# Arduino_NRF24_RevD.net
KiCad netlist of a schematic drawn in EAGLE
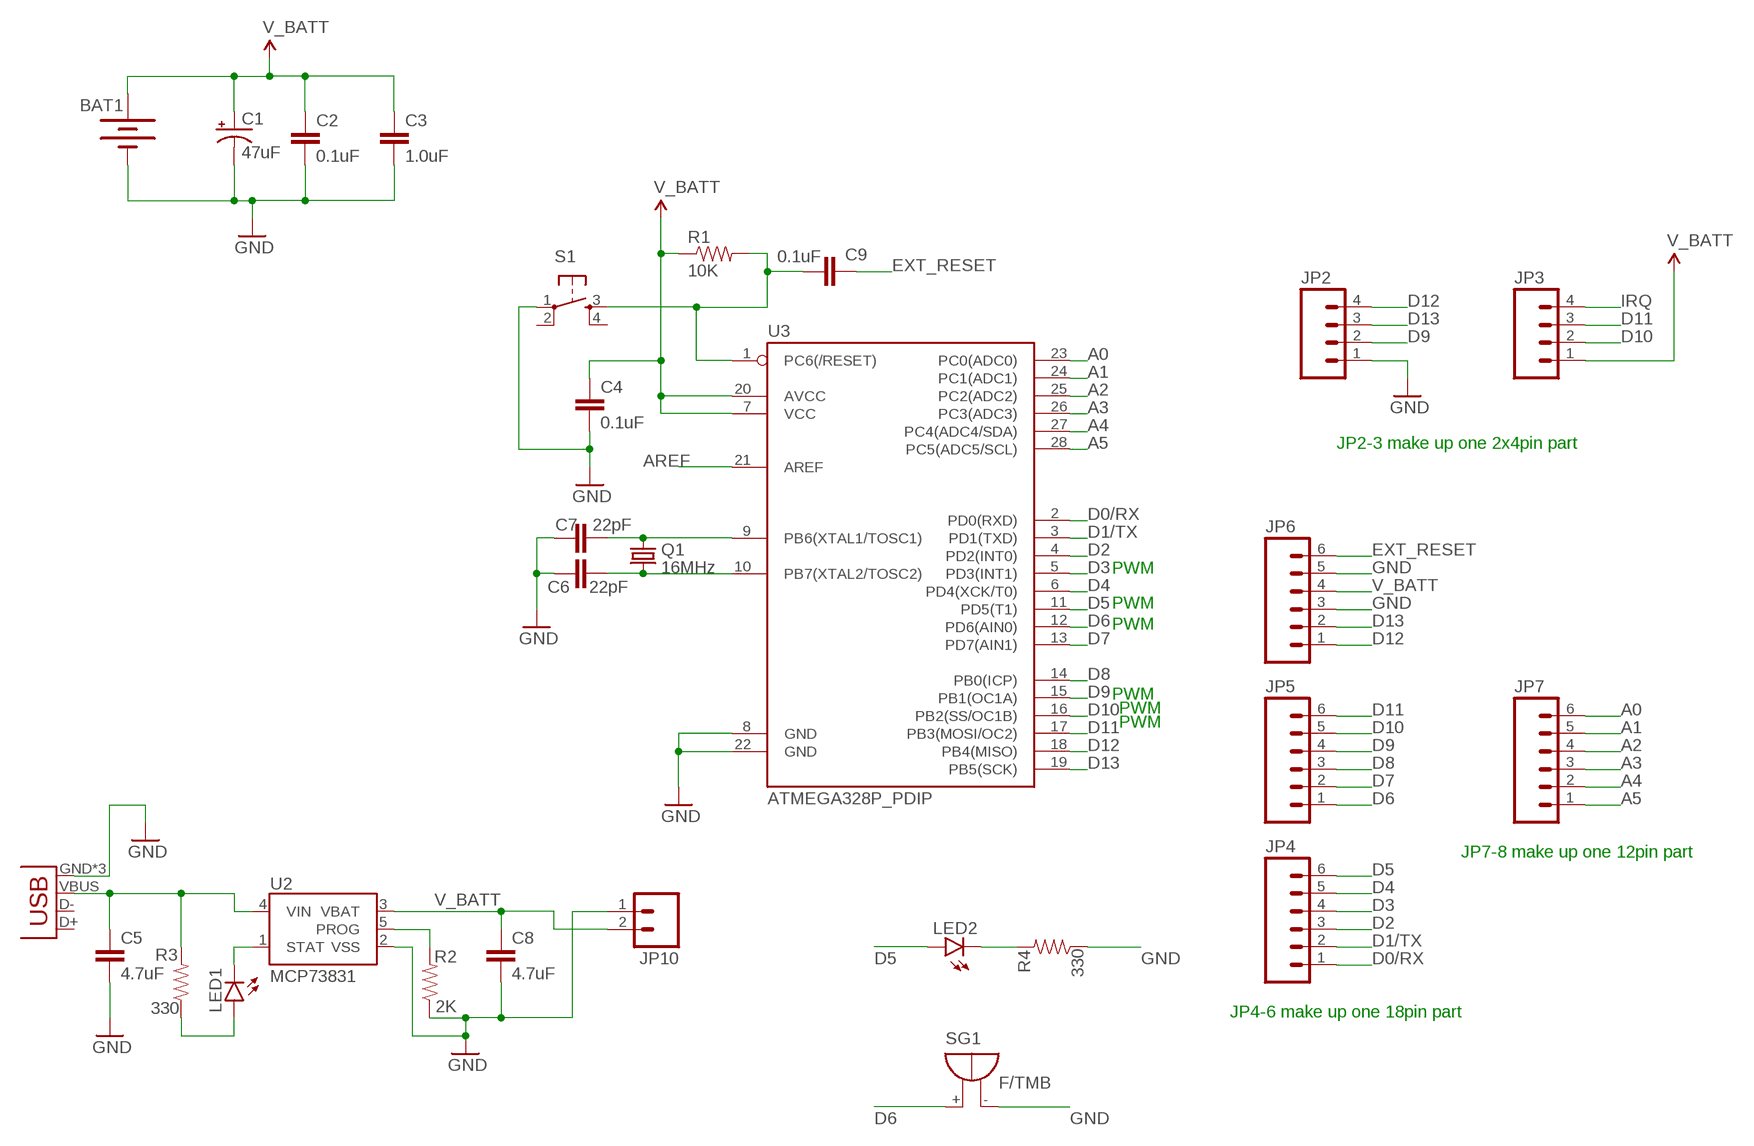
[diagram p0: schematic, sheet 1]

(export (version "E")
  (design (tool "Eeschema 10.0.6"))
  (components
    (comp (ref "BAT1")
      (value "20mm coincell")
      (footprint "eagle-import:BATTCON_20MM_4LEGS")
      (fields (field (name "MF") "KEYSTONE ELECTR") (field (name "MPN") "1065"))
      (libsource (lib "eagle-import") (part "BATTERY20MM_4LEGS"))
    )
    (comp (ref "C1")
      (value "47uF")
      (footprint "eagle-import:CPOL-RADIAL-100UF-25V")
      (fields (field (name "MPN") "MCTG470M1AB-0512P"))
      (libsource (lib "eagle-import") (part "CAP_POLPTH1"))
    )
    (comp (ref "C2")
      (value "0.1uF")
      (footprint "eagle-import:CAP-PTH-SMALLEZ")
      (fields (field (name "MF") "BC  COMPONENTS") (field (name "MPN") "K104K15X7RF5TL2"))
      (libsource (lib "eagle-import") (part "CAPEZ"))
    )
    (comp (ref "C3")
      (value "1.0uF")
      (footprint "eagle-import:CAP-PTH-SMALLEZ")
      (fields (field (name "MPN") "MCNP16V105M5X11"))
      (libsource (lib "eagle-import") (part "CAPEZ"))
    )
    (comp (ref "C4")
      (value "0.1uF")
      (footprint "eagle-import:CAP-PTH-SMALLEZ")
      (fields (field (name "MF") "BC  COMPONENTS") (field (name "MPN") "K104K15X7RF5TL2"))
      (libsource (lib "eagle-import") (part "CAPEZ"))
    )
    (comp (ref "C5")
      (value "4.7uF")
      (footprint "eagle-import:CAP-PTH-SMALLEZ")
      (fields (field (name "MF") "Multicomp Passives") (field (name "MPN") "MCLV4R7M1HB-0513-RH"))
      (libsource (lib "eagle-import") (part "CAPEZ"))
    )
    (comp (ref "C6")
      (value "22pF")
      (footprint "eagle-import:CAP-PTH-SMALLEZ")
      (fields (field (name "MPN") "MCCC50V220JNPO"))
      (libsource (lib "eagle-import") (part "CAPEZ"))
    )
    (comp (ref "C7")
      (value "22pF")
      (footprint "eagle-import:CAP-PTH-SMALLEZ")
      (fields (field (name "MPN") "MCCC50V220JNPO"))
      (libsource (lib "eagle-import") (part "CAPEZ"))
    )
    (comp (ref "C8")
      (value "4.7uF")
      (footprint "eagle-import:CAP-PTH-SMALLEZ")
      (fields (field (name "MF") "Multicomp Passives") (field (name "MPN") "MCLV4R7M1HB-0513-RH"))
      (libsource (lib "eagle-import") (part "CAPEZ"))
    )
    (comp (ref "C9")
      (value "0.1uF")
      (footprint "eagle-import:CAP-PTH-SMALLEZ")
      (fields (field (name "MF") "BC  COMPONENTS") (field (name "MPN") "K104K15X7RF5TL2"))
      (libsource (lib "eagle-import") (part "CAPEZ"))
    )
    (comp (ref "JP2")
      (value "M04PTH")
      (footprint "eagle-import:1X04")
      (fields (field (name "MPN") "BIM-INT-Y1X-0.4M-RS 4.21T W/M"))
      (libsource (lib "eagle-import") (part "M04PTH"))
    )
    (comp (ref "JP3")
      (value "M04PTH")
      (footprint "eagle-import:1X04")
      (fields (field (name "MPN") "BIM-INT-Y1X-0.4M-RS 4.21T W/M"))
      (libsource (lib "eagle-import") (part "M04PTH"))
    )
    (comp (ref "JP4")
      (value "M06SIP")
      (footprint "eagle-import:1X06")
      (fields (field (name "MPN") "BI1.5-H6.5-Y1X-0.6M-RS4.21T"))
      (libsource (lib "eagle-import") (part "M06SIP"))
    )
    (comp (ref "JP5")
      (value "M06SIP")
      (footprint "eagle-import:1X06")
      (fields (field (name "MPN") "BI1.5-H6.5-Y1X-0.6M-RS4.21T"))
      (libsource (lib "eagle-import") (part "M06SIP"))
    )
    (comp (ref "JP6")
      (value "M06SIP")
      (footprint "eagle-import:1X06")
      (fields (field (name "MPN") "BI1.5-H6.5-Y1X-0.6M-RS4.21T"))
      (libsource (lib "eagle-import") (part "M06SIP"))
    )
    (comp (ref "JP7")
      (value "M06SIP")
      (footprint "eagle-import:1X06")
      (fields (field (name "MPN") "BI1.5-H6.5-Y1X-0.6M-RS4.21T"))
      (libsource (lib "eagle-import") (part "M06SIP"))
    )
    (comp (ref "JP9")
      (value "USB-MICROB")
      (footprint "eagle-import:USB-MICROB")
      (fields (field (name "MPN") "USB3100-30-A"))
      (libsource (lib "eagle-import") (part "USB-MICROB"))
    )
    (comp (ref "JP10")
      (value "M02JST-PTH-2")
      (footprint "eagle-import:JST-2-PTH")
      (fields (field (name "MF") "MOLEX") (field (name "MPN") "26-60-4020"))
      (libsource (lib "eagle-import") (part "M02JST-PTH-2"))
    )
    (comp (ref "LED1")
      (value "LED5MM")
      (footprint "eagle-import:LED5MM")
      (fields (field (name "MPN") "C503B-BCN-CV0Z0461"))
      (libsource (lib "eagle-import") (part "LED5MM"))
    )
    (comp (ref "LED2")
      (value "LED5MM")
      (footprint "eagle-import:LED5MM")
      (fields (field (name "MPN") "C503B-BCN-CV0Z0461"))
      (libsource (lib "eagle-import") (part "LED5MM"))
    )
    (comp (ref "Q1")
      (value "16MHz")
      (footprint "eagle-import:HC49U-V")
      (fields (field (name "MPN") "ABLSG-16.000MHZ-D-2-Y-T") (field (name "OC_NEWARK") "01T1300"))
      (libsource (lib "eagle-import") (part "CRYSTALHC49U-V"))
    )
    (comp (ref "R1")
      (value "10K")
      (footprint "eagle-import:AXIAL-0.4")
      (fields (field (name "MF") "FARNELL") (field (name "MPN") "MC0063W0603510K"))
      (libsource (lib "eagle-import") (part "RESISTORPTH-1/4W"))
    )
    (comp (ref "R2")
      (value "2K")
      (footprint "eagle-import:AXIAL-0.4")
      (fields (field (name "MF") "MCM ELECTRONICS") (field (name "MPN") "34-2K"))
      (libsource (lib "eagle-import") (part "RESISTORPTH-1/4W"))
    )
    (comp (ref "R3")
      (value "330")
      (footprint "eagle-import:AXIAL-0.4")
      (fields (field (name "MF") "FARNELL") (field (name "MPN") "MCF 0.5W 330R"))
      (libsource (lib "eagle-import") (part "RESISTORPTH-1/4W"))
    )
    (comp (ref "R4")
      (value "330")
      (footprint "eagle-import:AXIAL-0.4")
      (fields (field (name "MF") "FARNELL") (field (name "MPN") "MCF 0.5W 330R"))
      (libsource (lib "eagle-import") (part "RESISTORPTH-1/4W"))
    )
    (comp (ref "S1")
      (value "TAC_SWITCHSMD")
      (footprint "eagle-import:TACTILE_SWITCH_SMD")
      (fields (field (name "MPN") "1571218-6"))
      (libsource (lib "eagle-import") (part "TAC_SWITCHSMD"))
    )
    (comp (ref "SG1")
      (value "F/TMB")
      (footprint "eagle-import:F_TMB")
      (fields (field (name "MPN") "MCKPI-G2913L-3973") (field (name "OC_NEWARK") "25R0655"))
      (libsource (lib "eagle-import") (part "F/TMB"))
    )
    (comp (ref "U2")
      (value "MCP73831")
      (footprint "eagle-import:SOT23-5")
      (fields (field (name "MPN") "MCP73831T-2ACI/OT"))
      (libsource (lib "eagle-import") (part "MCP73831"))
    )
    (comp (ref "U3")
      (value "ATMEGA328P_PDIP")
      (footprint "eagle-import:DIL28-3")
      (fields (field (name "MPN") "ATMEGA328P-PU"))
      (libsource (lib "eagle-import") (part "ATMEGA328P_PDIP"))
    )
  )
  (nets
    (net (code "1") (name "/A0") (class "Default")
      (node (ref "JP7") (pin "6") (pinfunction "6_6") (pintype "passive"))
      (node (ref "U3") (pin "23") (pinfunction "PC0(ADC0)_23") (pintype "bidirectional"))
    )
    (net (code "2") (name "/A1") (class "Default")
      (node (ref "JP7") (pin "5") (pinfunction "5_5") (pintype "passive"))
      (node (ref "U3") (pin "24") (pinfunction "PC1(ADC1)_24") (pintype "bidirectional"))
    )
    (net (code "3") (name "/A2") (class "Default")
      (node (ref "JP7") (pin "4") (pinfunction "4_4") (pintype "passive"))
      (node (ref "U3") (pin "25") (pinfunction "PC2(ADC2)_25") (pintype "bidirectional"))
    )
    (net (code "4") (name "/A3") (class "Default")
      (node (ref "JP7") (pin "3") (pinfunction "3_3") (pintype "passive"))
      (node (ref "U3") (pin "26") (pinfunction "PC3(ADC3)_26") (pintype "bidirectional"))
    )
    (net (code "5") (name "/A4") (class "Default")
      (node (ref "JP7") (pin "2") (pinfunction "2_2") (pintype "passive"))
      (node (ref "U3") (pin "27") (pinfunction "PC4(ADC4/SDA)_27") (pintype "bidirectional"))
    )
    (net (code "6") (name "/A5") (class "Default")
      (node (ref "JP7") (pin "1") (pinfunction "1_1") (pintype "passive"))
      (node (ref "U3") (pin "28") (pinfunction "PC5(ADC5/SCL)_28") (pintype "bidirectional"))
    )
    (net (code "7") (name "/AREF") (class "Default")
      (node (ref "U3") (pin "21") (pinfunction "AREF_21") (pintype "bidirectional"))
    )
    (net (code "8") (name "/D0{slash}RX") (class "Default")
      (node (ref "JP4") (pin "1") (pinfunction "1_1") (pintype "passive"))
      (node (ref "U3") (pin "2") (pinfunction "PD0(RXD)_2") (pintype "bidirectional"))
    )
    (net (code "9") (name "/D1{slash}TX") (class "Default")
      (node (ref "JP4") (pin "2") (pinfunction "2_2") (pintype "passive"))
      (node (ref "U3") (pin "3") (pinfunction "PD1(TXD)_3") (pintype "bidirectional"))
    )
    (net (code "10") (name "/D2") (class "Default")
      (node (ref "JP4") (pin "3") (pinfunction "3_3") (pintype "passive"))
      (node (ref "U3") (pin "4") (pinfunction "PD2(INT0)_4") (pintype "bidirectional"))
    )
    (net (code "11") (name "/D3") (class "Default")
      (node (ref "JP4") (pin "4") (pinfunction "4_4") (pintype "passive"))
      (node (ref "U3") (pin "5") (pinfunction "PD3(INT1)_5") (pintype "bidirectional"))
    )
    (net (code "12") (name "/D4") (class "Default")
      (node (ref "JP4") (pin "5") (pinfunction "5_5") (pintype "passive"))
      (node (ref "U3") (pin "6") (pinfunction "PD4(XCK/T0)_6") (pintype "bidirectional"))
    )
    (net (code "13") (name "/D5") (class "Default")
      (node (ref "JP4") (pin "6") (pinfunction "6_6") (pintype "passive"))
      (node (ref "LED2") (pin "A") (pinfunction "A_A") (pintype "passive"))
      (node (ref "U3") (pin "11") (pinfunction "PD5(T1)_11") (pintype "bidirectional"))
    )
    (net (code "14") (name "/D6") (class "Default")
      (node (ref "JP5") (pin "1") (pinfunction "1_1") (pintype "passive"))
      (node (ref "SG1") (pin "+") (pinfunction "+_+") (pintype "passive"))
      (node (ref "U3") (pin "12") (pinfunction "PD6(AIN0)_12") (pintype "bidirectional"))
    )
    (net (code "15") (name "/D7") (class "Default")
      (node (ref "JP5") (pin "2") (pinfunction "2_2") (pintype "passive"))
      (node (ref "U3") (pin "13") (pinfunction "PD7(AIN1)_13") (pintype "bidirectional"))
    )
    (net (code "16") (name "/D8") (class "Default")
      (node (ref "JP5") (pin "3") (pinfunction "3_3") (pintype "passive"))
      (node (ref "U3") (pin "14") (pinfunction "PB0(ICP)_14") (pintype "bidirectional"))
    )
    (net (code "17") (name "/D9") (class "Default")
      (node (ref "JP2") (pin "2") (pinfunction "2_2") (pintype "passive"))
      (node (ref "JP5") (pin "4") (pinfunction "4_4") (pintype "passive"))
      (node (ref "U3") (pin "15") (pinfunction "PB1(OC1A)_15") (pintype "bidirectional"))
    )
    (net (code "18") (name "/D10") (class "Default")
      (node (ref "JP3") (pin "2") (pinfunction "2_2") (pintype "passive"))
      (node (ref "JP5") (pin "5") (pinfunction "5_5") (pintype "passive"))
      (node (ref "U3") (pin "16") (pinfunction "PB2(SS/OC1B)_16") (pintype "bidirectional"))
    )
    (net (code "19") (name "/D11") (class "Default")
      (node (ref "JP3") (pin "3") (pinfunction "3_3") (pintype "passive"))
      (node (ref "JP5") (pin "6") (pinfunction "6_6") (pintype "passive"))
      (node (ref "U3") (pin "17") (pinfunction "PB3(MOSI/OC2)_17") (pintype "bidirectional"))
    )
    (net (code "20") (name "/D12") (class "Default")
      (node (ref "JP2") (pin "4") (pinfunction "4_4") (pintype "passive"))
      (node (ref "JP6") (pin "1") (pinfunction "1_1") (pintype "passive"))
      (node (ref "U3") (pin "18") (pinfunction "PB4(MISO)_18") (pintype "bidirectional"))
    )
    (net (code "21") (name "/D13") (class "Default")
      (node (ref "JP2") (pin "3") (pinfunction "3_3") (pintype "passive"))
      (node (ref "JP6") (pin "2") (pinfunction "2_2") (pintype "passive"))
      (node (ref "U3") (pin "19") (pinfunction "PB5(SCK)_19") (pintype "bidirectional"))
    )
    (net (code "22") (name "/EXT_RESET") (class "Default")
      (node (ref "C9") (pin "1") (pinfunction "1_1") (pintype "passive"))
      (node (ref "JP6") (pin "6") (pinfunction "6_6") (pintype "passive"))
    )
    (net (code "23") (name "/IRQ") (class "Default")
      (node (ref "JP3") (pin "4") (pinfunction "4_4") (pintype "passive"))
    )
    (net (code "24") (name "GND") (class "Default")
      (node (ref "BAT1") (pin "2") (pinfunction "-_2") (pintype "power_in"))
      (node (ref "C1") (pin "2") (pinfunction "-_2") (pintype "passive"))
      (node (ref "C2") (pin "2") (pinfunction "2_2") (pintype "passive"))
      (node (ref "C3") (pin "2") (pinfunction "2_2") (pintype "passive"))
      (node (ref "C4") (pin "2") (pinfunction "2_2") (pintype "passive"))
      (node (ref "C5") (pin "2") (pinfunction "2_2") (pintype "passive"))
      (node (ref "C6") (pin "1") (pinfunction "1_1") (pintype "passive"))
      (node (ref "C7") (pin "2") (pinfunction "2_2") (pintype "passive"))
      (node (ref "C8") (pin "2") (pinfunction "2_2") (pintype "passive"))
      (node (ref "JP10") (pin "1") (pinfunction "1_1") (pintype "passive"))
      (node (ref "JP2") (pin "1") (pinfunction "1_1") (pintype "passive"))
      (node (ref "JP6") (pin "3") (pinfunction "3_3") (pintype "passive"))
      (node (ref "JP6") (pin "5") (pinfunction "5_5") (pintype "passive"))
      (node (ref "JP9") (pin "GND") (pinfunction "GND_GND") (pintype "bidirectional"))
      (node (ref "JP9") (pin "MT1") (pinfunction "GND_MT1") (pintype "bidirectional"))
      (node (ref "JP9") (pin "MT2") (pinfunction "GND_MT2") (pintype "bidirectional"))
      (node (ref "R2") (pin "P$1") (pinfunction "1_P$1") (pintype "passive"))
      (node (ref "R4") (pin "P$1") (pinfunction "1_P$1") (pintype "passive"))
      (node (ref "S1") (pin "1") (pinfunction "1_1") (pintype "passive"))
      (node (ref "SG1") (pin "-") (pinfunction "-_-") (pintype "passive"))
      (node (ref "U2") (pin "2") (pinfunction "VSS_2") (pintype "power_in"))
      (node (ref "U3") (pin "22") (pinfunction "GND_22") (pintype "bidirectional"))
      (node (ref "U3") (pin "8") (pinfunction "GND_8") (pintype "bidirectional"))
    )
    (net (code "25") (name "Net-(LED1-C)") (class "Default")
      (node (ref "LED1") (pin "K") (pinfunction "C_K") (pintype "passive"))
      (node (ref "U2") (pin "1") (pinfunction "STAT_1") (pintype "output"))
    )
    (net (code "26") (name "Net-(LED2-C)") (class "Default")
      (node (ref "LED2") (pin "K") (pinfunction "C_K") (pintype "passive"))
      (node (ref "R4") (pin "P$2") (pinfunction "2_P$2") (pintype "passive"))
    )
    (net (code "27") (name "Net-(R1-2)") (class "Default")
      (node (ref "C9") (pin "2") (pinfunction "2_2") (pintype "passive"))
      (node (ref "R1") (pin "P$2") (pinfunction "2_P$2") (pintype "passive"))
      (node (ref "S1") (pin "3") (pinfunction "3_3") (pintype "passive"))
      (node (ref "U3") (pin "1") (pinfunction "PC6(/RESET)_1") (pintype "bidirectional"))
    )
    (net (code "28") (name "Net-(R2-2)") (class "Default")
      (node (ref "R2") (pin "P$2") (pinfunction "2_P$2") (pintype "passive"))
      (node (ref "U2") (pin "5") (pinfunction "PROG_5") (pintype "input"))
    )
    (net (code "29") (name "Net-(R3-1)") (class "Default")
      (node (ref "LED1") (pin "A") (pinfunction "A_A") (pintype "passive"))
      (node (ref "R3") (pin "P$1") (pinfunction "1_P$1") (pintype "passive"))
    )
    (net (code "30") (name "Net-(R3-2)") (class "Default")
      (node (ref "C5") (pin "1") (pinfunction "1_1") (pintype "passive"))
      (node (ref "JP9") (pin "VBUS") (pinfunction "VBUS_VBUS") (pintype "bidirectional"))
      (node (ref "R3") (pin "P$2") (pinfunction "2_P$2") (pintype "passive"))
      (node (ref "U2") (pin "4") (pinfunction "VIN_4") (pintype "power_in"))
    )
    (net (code "31") (name "Net-(U3-PB6(XTAL1{slash}TOSC1))") (class "Default")
      (node (ref "C7") (pin "1") (pinfunction "1_1") (pintype "passive"))
      (node (ref "Q1") (pin "1") (pinfunction "1_1") (pintype "passive"))
      (node (ref "U3") (pin "9") (pinfunction "PB6(XTAL1/TOSC1)_9") (pintype "bidirectional"))
    )
    (net (code "32") (name "Net-(U3-PB7(XTAL2{slash}TOSC2))") (class "Default")
      (node (ref "C6") (pin "2") (pinfunction "2_2") (pintype "passive"))
      (node (ref "Q1") (pin "2") (pinfunction "2_2") (pintype "passive"))
      (node (ref "U3") (pin "10") (pinfunction "PB7(XTAL2/TOSC2)_10") (pintype "bidirectional"))
    )
    (net (code "33") (name "V_BATT") (class "Default")
      (node (ref "BAT1") (pin "1") (pinfunction "+_1") (pintype "power_in"))
      (node (ref "C1") (pin "1") (pinfunction "+_1") (pintype "passive"))
      (node (ref "C2") (pin "1") (pinfunction "1_1") (pintype "passive"))
      (node (ref "C3") (pin "1") (pinfunction "1_1") (pintype "passive"))
      (node (ref "C4") (pin "1") (pinfunction "1_1") (pintype "passive"))
      (node (ref "C8") (pin "1") (pinfunction "1_1") (pintype "passive"))
      (node (ref "JP10") (pin "2") (pinfunction "2_2") (pintype "passive"))
      (node (ref "JP3") (pin "1") (pinfunction "1_1") (pintype "passive"))
      (node (ref "JP6") (pin "4") (pinfunction "4_4") (pintype "passive"))
      (node (ref "R1") (pin "P$1") (pinfunction "1_P$1") (pintype "passive"))
      (node (ref "U2") (pin "3") (pinfunction "VBAT_3") (pintype "power_in"))
      (node (ref "U3") (pin "20") (pinfunction "AVCC_20") (pintype "bidirectional"))
      (node (ref "U3") (pin "7") (pinfunction "VCC_7") (pintype "bidirectional"))
    )
    (net (code "34") (name "unconnected-(JP9-PadD+)") (class "Default")
      (node (ref "JP9") (pin "D+") (pinfunction "D+_D+") (pintype "bidirectional"))
    )
    (net (code "35") (name "unconnected-(JP9-PadD-)") (class "Default")
      (node (ref "JP9") (pin "D-") (pinfunction "D-_D-") (pintype "bidirectional"))
    )
    (net (code "36") (name "unconnected-(S1-Pad2)") (class "Default")
      (node (ref "S1") (pin "2") (pinfunction "2_2") (pintype "passive"))
    )
    (net (code "37") (name "unconnected-(S1-Pad4)") (class "Default")
      (node (ref "S1") (pin "4") (pinfunction "4_4") (pintype "passive"))
    )
  )
)
